# ServoPower.net
KiCad netlist of a schematic drawn in Altium Designer
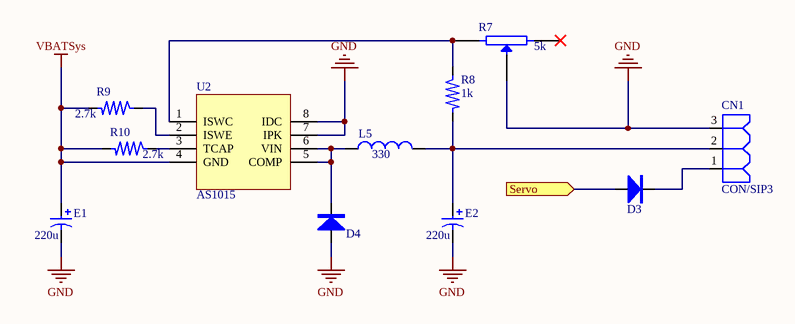
[diagram p0: ServoPower.SchDoc]

(export (version "E")
  (design (tool "Eeschema 10.0.6"))
  (components
    (comp (ref "CN1")
      (value "CON/SIP3")
      (footprint "HDR1X3")
      (libsource (lib "LQ_Integrated_Library") (part "CON/SIP3"))
    )
    (comp (ref "D3")
      (value "DIODE")
      (footprint "DO-214")
      (description "二极管")
      (libsource (lib "LQ_Integrated_Library") (part "DIODE"))
    )
    (comp (ref "D4")
      (value "DIODE")
      (footprint "DO-214")
      (description "二极管")
      (libsource (lib "") (part "DIODE_1"))
    )
    (comp (ref "E1")
      (value "220u")
      (footprint "CAP-E SMD-D")
      (description "极性电容")
      (libsource (lib "LQ_Integrated_Library") (part "Capacitor-Polarity"))
    )
    (comp (ref "E2")
      (value "220u")
      (footprint "CAP-E SMD-D")
      (description "极性电容")
      (libsource (lib "LQ_Integrated_Library") (part "Capacitor-Polarity"))
    )
    (comp (ref "L5")
      (value "330")
      (footprint "L7X7")
      (description "Inductor")
      (libsource (lib "LQ_Integrated_Library") (part "INDUCTOR"))
    )
    (comp (ref "R7")
      (value "5k")
      (footprint "RES ADJ-3296W")
      (description "滑动变阻器")
      (libsource (lib "LQ_Integrated_Library") (part "Resistor-Potentiometer"))
    )
    (comp (ref "R8")
      (value "1k")
      (footprint "R0603")
      (description "电阻")
      (libsource (lib "LQ_Integrated_Library") (part "Resistor"))
    )
    (comp (ref "R9")
      (value "2.7k")
      (footprint "R0603")
      (description "电阻")
      (libsource (lib "LQ_Integrated_Library") (part "Resistor"))
    )
    (comp (ref "R10")
      (value "2.7k")
      (footprint "R0603")
      (description "电阻")
      (libsource (lib "LQ_Integrated_Library") (part "Resistor"))
    )
    (comp (ref "U2")
      (value "AS1015")
      (footprint "SOIC8")
      (description "充电电路芯片")
      (libsource (lib "LQ_Integrated_Library") (part "MC34603"))
    )
  )
  (nets
    (net (code "1") (name "/Servo") (class "Default")
      (node (ref "D3") (pin "1") (pinfunction "A_1") (pintype "passive"))
    )
    (net (code "2") (name "GND") (class "Default")
      (node (ref "CN1") (pin "3") (pintype "passive"))
      (node (ref "D4") (pin "1") (pinfunction "A_1") (pintype "passive"))
      (node (ref "E1") (pin "2") (pinfunction "2_2") (pintype "passive"))
      (node (ref "E2") (pin "2") (pinfunction "2_2") (pintype "passive"))
      (node (ref "R7") (pin "3") (pinfunction "W_3") (pintype "passive"))
      (node (ref "U2") (pin "7") (pinfunction "IPK_7") (pintype "passive"))
      (node (ref "U2") (pin "8") (pinfunction "IDC_8") (pintype "passive"))
    )
    (net (code "3") (name "Net-(CN1-Pad2)") (class "Default")
      (node (ref "CN1") (pin "2") (pintype "passive"))
      (node (ref "E2") (pin "1") (pinfunction "1_1") (pintype "passive"))
      (node (ref "L5") (pin "2") (pinfunction "2_2") (pintype "passive"))
      (node (ref "R8") (pin "1") (pinfunction "1_1") (pintype "passive"))
    )
    (net (code "4") (name "Net-(D3-K)") (class "Default")
      (node (ref "CN1") (pin "1") (pintype "passive"))
      (node (ref "D3") (pin "2") (pinfunction "K_2") (pintype "passive"))
    )
    (net (code "5") (name "Net-(D4-K)") (class "Default")
      (node (ref "D4") (pin "2") (pinfunction "K_2") (pintype "passive"))
      (node (ref "L5") (pin "1") (pinfunction "1_1") (pintype "passive"))
      (node (ref "U2") (pin "5") (pinfunction "COMP_5") (pintype "passive"))
      (node (ref "U2") (pin "6") (pinfunction "VIN_6") (pintype "passive"))
    )
    (net (code "6") (name "Net-(U2-ISWC)") (class "Default")
      (node (ref "R7") (pin "2") (pinfunction "2_2") (pintype "passive"))
      (node (ref "R8") (pin "2") (pinfunction "2_2") (pintype "passive"))
      (node (ref "U2") (pin "1") (pinfunction "ISWC_1") (pintype "passive"))
    )
    (net (code "7") (name "Net-(U2-ISWE)") (class "Default")
      (node (ref "R9") (pin "2") (pinfunction "2_2") (pintype "passive"))
      (node (ref "U2") (pin "2") (pinfunction "ISWE_2") (pintype "passive"))
    )
    (net (code "8") (name "Net-(U2-TCAP)") (class "Default")
      (node (ref "R10") (pin "2") (pinfunction "2_2") (pintype "passive"))
      (node (ref "U2") (pin "3") (pinfunction "TCAP_3") (pintype "passive"))
    )
    (net (code "9") (name "VBATSys") (class "Default")
      (node (ref "E1") (pin "1") (pinfunction "1_1") (pintype "passive"))
      (node (ref "R10") (pin "1") (pinfunction "1_1") (pintype "passive"))
      (node (ref "R9") (pin "1") (pinfunction "1_1") (pintype "passive"))
      (node (ref "U2") (pin "4") (pinfunction "GND_4") (pintype "passive"))
    )
    (net (code "10") (name "unconnected-(R7-Pad1)") (class "Default")
      (node (ref "R7") (pin "1") (pinfunction "1_1") (pintype "passive+no_connect"))
    )
  )
)
